# Aroca_EPS-v_2_0.net
KiCad netlist of a schematic drawn in EAGLE
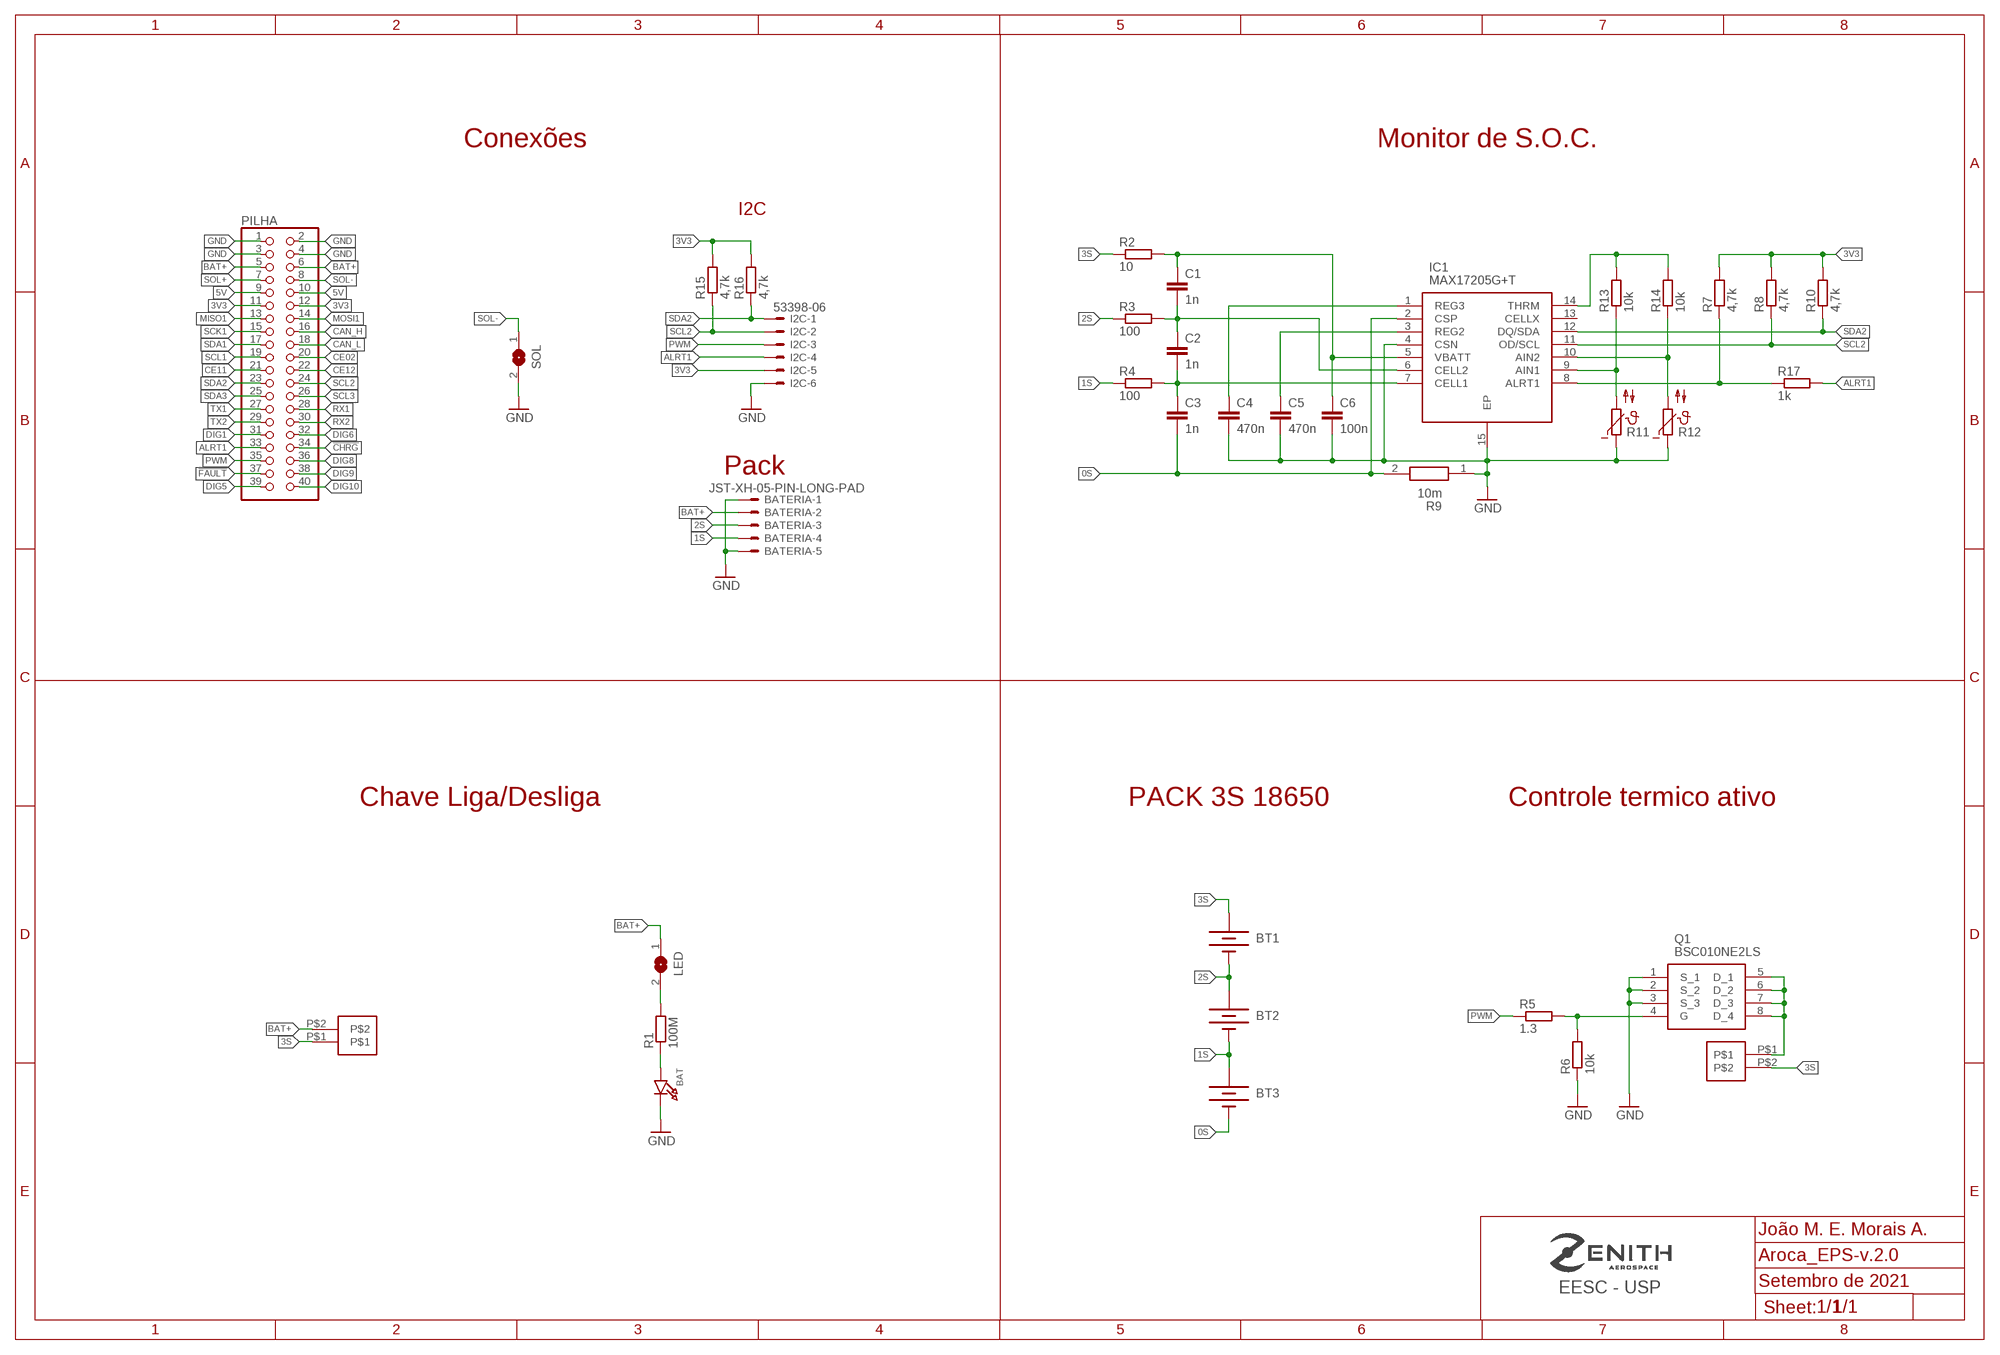
[diagram p0: schematic, sheet 1]

(export (version "E")
  (design (tool "Eeschema 10.0.6"))
  (components
    (comp (ref "BAT")
      (value "LED1206")
      (footprint "eagle-import:CHIPLED_1206")
      (libsource (lib "eagle-import") (part "LED1206"))
    )
    (comp (ref "BATERIA")
      (value "JST-XH-05-PIN-LONG-PAD")
      (footprint "eagle-import:JST-XH-05-PACKAGE-LONG-PAD")
      (libsource (lib "eagle-import") (part "JST-XH-05-PIN-LONG-PAD"))
    )
    (comp (ref "BT1")
      (value "BATTERY-18650")
      (footprint "eagle-import:BATTERY_18650-HOLDER")
      (libsource (lib "eagle-import") (part "BATTERY-18650"))
    )
    (comp (ref "BT2")
      (value "BATTERY-18650")
      (footprint "eagle-import:BATTERY_18650-HOLDER")
      (libsource (lib "eagle-import") (part "BATTERY-18650"))
    )
    (comp (ref "BT3")
      (value "BATTERY-18650")
      (footprint "eagle-import:BATTERY_18650-HOLDER")
      (libsource (lib "eagle-import") (part "BATTERY-18650"))
    )
    (comp (ref "C1")
      (value "1n")
      (footprint "eagle-import:C0805")
      (libsource (lib "eagle-import") (part "C-EUC0805"))
    )
    (comp (ref "C2")
      (value "1n")
      (footprint "eagle-import:C0805")
      (libsource (lib "eagle-import") (part "C-EUC0805"))
    )
    (comp (ref "C3")
      (value "1n")
      (footprint "eagle-import:C0805")
      (libsource (lib "eagle-import") (part "C-EUC0805"))
    )
    (comp (ref "C4")
      (value "470n")
      (footprint "eagle-import:C0805")
      (libsource (lib "eagle-import") (part "C-EUC0805"))
    )
    (comp (ref "C5")
      (value "470n")
      (footprint "eagle-import:C0805")
      (libsource (lib "eagle-import") (part "C-EUC0805"))
    )
    (comp (ref "C6")
      (value "100n")
      (footprint "eagle-import:C0805")
      (libsource (lib "eagle-import") (part "C-EUC0805"))
    )
    (comp (ref "I2C")
      (value "53398-06")
      (footprint "eagle-import:53398-06")
      (fields (field (name "MF") "MOLEX"))
      (libsource (lib "eagle-import") (part "53?-06398"))
    )
    (comp (ref "IC1")
      (value "MAX17205G+T")
      (footprint "eagle-import:SON40P300X300X80-15N")
      (fields (field (name "MOUSER_PART_NUMBER") "700-MAX17205G+T"))
      (libsource (lib "eagle-import") (part "MAX17205G+T"))
    )
    (comp (ref "LED")
      (value "SOLDERJUMPERREFLOW_NOPASTE")
      (footprint "eagle-import:SOLDERJUMPER_REFLOW_NOPASTE")
      (libsource (lib "eagle-import") (part "SOLDERJUMPERREFLOW_NOPASTE"))
    )
    (comp (ref "PILHA")
      (value "PINHD-2X20")
      (footprint "eagle-import:2X20")
      (libsource (lib "eagle-import") (part "PINHD-2X20"))
    )
    (comp (ref "Q1")
      (value "BSC010NE2LS")
      (footprint "eagle-import:PG-TDSON-8")
      (fields (field (name "MOUSER_PART_NUMBER") "726-BSC010NE2LS"))
      (libsource (lib "eagle-import") (part "BSC010NE2LS"))
    )
    (comp (ref "R1")
      (value "100M")
      (footprint "eagle-import:R0805")
      (libsource (lib "eagle-import") (part "R-EU_R0805"))
    )
    (comp (ref "R2")
      (value "10")
      (footprint "eagle-import:0204_7")
      (libsource (lib "eagle-import") (part "R-EU_0204/7"))
    )
    (comp (ref "R3")
      (value "100")
      (footprint "eagle-import:0204_7")
      (libsource (lib "eagle-import") (part "R-EU_0204/7"))
    )
    (comp (ref "R4")
      (value "100")
      (footprint "eagle-import:0204_7")
      (libsource (lib "eagle-import") (part "R-EU_0204/7"))
    )
    (comp (ref "R5")
      (value "1.3")
      (footprint "eagle-import:R0805")
      (libsource (lib "eagle-import") (part "R-EU_R0805"))
    )
    (comp (ref "R6")
      (value "10k")
      (footprint "eagle-import:R0805")
      (libsource (lib "eagle-import") (part "R-EU_R0805"))
    )
    (comp (ref "R7")
      (value "4,7k")
      (footprint "eagle-import:R0805")
      (libsource (lib "eagle-import") (part "R-EU_R0805"))
    )
    (comp (ref "R8")
      (value "4,7k")
      (footprint "eagle-import:R0805")
      (libsource (lib "eagle-import") (part "R-EU_R0805"))
    )
    (comp (ref "R9")
      (value "10m")
      (footprint "eagle-import:GMR320HJBFA10L0")
      (fields
        (field (name "MANUFACTURER_PART_NUMBER") "GMR320HJBFA10L0")
        (field (name "MOUSER_PART_NUMBER") "755-GMR320HJBFA10L0")
      )
      (libsource (lib "eagle-import") (part "GMR320HJBFA10L0"))
    )
    (comp (ref "R10")
      (value "4,7k")
      (footprint "eagle-import:R0805")
      (libsource (lib "eagle-import") (part "R-EU_R0805"))
    )
    (comp (ref "R11")
      (value "NTC640")
      (footprint "eagle-import:P640")
      (libsource (lib "eagle-import") (part "NTC640"))
    )
    (comp (ref "R12")
      (value "NTC640")
      (footprint "eagle-import:P640")
      (libsource (lib "eagle-import") (part "NTC640"))
    )
    (comp (ref "R13")
      (value "10k")
      (footprint "eagle-import:R0805")
      (libsource (lib "eagle-import") (part "R-EU_R0805"))
    )
    (comp (ref "R14")
      (value "10k")
      (footprint "eagle-import:R0805")
      (libsource (lib "eagle-import") (part "R-EU_R0805"))
    )
    (comp (ref "R15")
      (value "4,7k")
      (footprint "eagle-import:R0805")
      (libsource (lib "eagle-import") (part "R-EU_R0805"))
    )
    (comp (ref "R16")
      (value "4,7k")
      (footprint "eagle-import:R0805")
      (libsource (lib "eagle-import") (part "R-EU_R0805"))
    )
    (comp (ref "R17")
      (value "1k")
      (footprint "eagle-import:R0805")
      (libsource (lib "eagle-import") (part "R-EU_R0805"))
    )
    (comp (ref "SOL")
      (value "SOLDERJUMPERREFLOW_NOPASTE")
      (footprint "eagle-import:SOLDERJUMPER_REFLOW_NOPASTE")
      (libsource (lib "eagle-import") (part "SOLDERJUMPERREFLOW_NOPASTE"))
    )
    (comp (ref "U$1")
      (value "S02B-XASS-1")
      (footprint "eagle-import:S02B-XASS-1")
      (libsource (lib "eagle-import") (part "S02B-XASS-1"))
    )
    (comp (ref "U$2")
      (value "B02B-XASK-1")
      (footprint "eagle-import:B02B-XASK-1")
      (libsource (lib "eagle-import") (part "B02B-XASK-1"))
    )
  )
  (nets
    (net (code "1") (name "/~{CHRG}") (class "Default")
      (node (ref "PILHA") (pin "34") (pinfunction "34_34") (pintype "passive"))
    )
    (net (code "2") (name "/~{FAULT}") (class "Default")
      (node (ref "PILHA") (pin "37") (pinfunction "37_37") (pintype "passive"))
    )
    (net (code "3") (name "0S") (class "Default")
      (node (ref "BT3") (pin "GND@1") (pinfunction "-_GND@1") (pintype "power_in"))
      (node (ref "C3") (pin "2") (pinfunction "2_2") (pintype "passive"))
      (node (ref "IC1") (pin "2") (pinfunction "CSP_2") (pintype "bidirectional"))
      (node (ref "R9") (pin "2") (pinfunction "2_2") (pintype "bidirectional"))
    )
    (net (code "4") (name "1S") (class "Default")
      (node (ref "BATERIA") (pin "4") (pinfunction "S_4") (pintype "passive"))
      (node (ref "BT2") (pin "GND@1") (pinfunction "-_GND@1") (pintype "power_in"))
      (node (ref "BT3") (pin "PWR@1") (pinfunction "+_PWR@1") (pintype "power_in"))
      (node (ref "R4") (pin "1") (pinfunction "1_1") (pintype "passive"))
    )
    (net (code "5") (name "2S") (class "Default")
      (node (ref "BATERIA") (pin "3") (pinfunction "S_3") (pintype "passive"))
      (node (ref "BT1") (pin "GND@1") (pinfunction "-_GND@1") (pintype "power_in"))
      (node (ref "BT2") (pin "PWR@1") (pinfunction "+_PWR@1") (pintype "power_in"))
      (node (ref "R3") (pin "1") (pinfunction "1_1") (pintype "passive"))
    )
    (net (code "6") (name "3S") (class "Default")
      (node (ref "BT1") (pin "PWR@1") (pinfunction "+_PWR@1") (pintype "power_in"))
      (node (ref "R2") (pin "1") (pinfunction "1_1") (pintype "passive"))
      (node (ref "U$1") (pin "P$1") (pinfunction "P$1_P$1") (pintype "bidirectional"))
      (node (ref "U$2") (pin "P$2") (pinfunction "P$2_P$2") (pintype "bidirectional"))
    )
    (net (code "7") (name "3V3") (class "Default")
      (node (ref "I2C") (pin "5") (pinfunction "S_5") (pintype "passive"))
      (node (ref "PILHA") (pin "11") (pinfunction "11_11") (pintype "passive"))
      (node (ref "PILHA") (pin "12") (pinfunction "12_12") (pintype "passive"))
      (node (ref "R10") (pin "2") (pinfunction "2_2") (pintype "passive"))
      (node (ref "R15") (pin "2") (pinfunction "2_2") (pintype "passive"))
      (node (ref "R16") (pin "2") (pinfunction "2_2") (pintype "passive"))
      (node (ref "R7") (pin "2") (pinfunction "2_2") (pintype "passive"))
      (node (ref "R8") (pin "2") (pinfunction "2_2") (pintype "passive"))
    )
    (net (code "8") (name "5V") (class "Default")
      (node (ref "PILHA") (pin "10") (pinfunction "10_10") (pintype "passive"))
      (node (ref "PILHA") (pin "9") (pinfunction "9_9") (pintype "passive"))
    )
    (net (code "9") (name "ALRT1") (class "Default")
      (node (ref "I2C") (pin "4") (pinfunction "S_4") (pintype "passive"))
      (node (ref "PILHA") (pin "33") (pinfunction "33_33") (pintype "passive"))
      (node (ref "R17") (pin "2") (pinfunction "2_2") (pintype "passive"))
    )
    (net (code "10") (name "BAT+") (class "Default")
      (node (ref "BATERIA") (pin "2") (pinfunction "S_2") (pintype "passive"))
      (node (ref "LED") (pin "1") (pinfunction "1_1") (pintype "passive"))
      (node (ref "PILHA") (pin "5") (pinfunction "5_5") (pintype "passive"))
      (node (ref "PILHA") (pin "6") (pinfunction "6_6") (pintype "passive"))
      (node (ref "U$1") (pin "P$2") (pinfunction "P$2_P$2") (pintype "bidirectional"))
    )
    (net (code "11") (name "CAN_H") (class "Default")
      (node (ref "PILHA") (pin "16") (pinfunction "16_16") (pintype "passive"))
    )
    (net (code "12") (name "CAN_L") (class "Default")
      (node (ref "PILHA") (pin "18") (pinfunction "18_18") (pintype "passive"))
    )
    (net (code "13") (name "CE02") (class "Default")
      (node (ref "PILHA") (pin "20") (pinfunction "20_20") (pintype "passive"))
    )
    (net (code "14") (name "CE11") (class "Default")
      (node (ref "PILHA") (pin "21") (pinfunction "21_21") (pintype "passive"))
    )
    (net (code "15") (name "CE12") (class "Default")
      (node (ref "PILHA") (pin "22") (pinfunction "22_22") (pintype "passive"))
    )
    (net (code "16") (name "DIG1") (class "Default")
      (node (ref "PILHA") (pin "31") (pinfunction "31_31") (pintype "passive"))
    )
    (net (code "17") (name "DIG5") (class "Default")
      (node (ref "PILHA") (pin "39") (pinfunction "39_39") (pintype "passive"))
    )
    (net (code "18") (name "DIG6") (class "Default")
      (node (ref "PILHA") (pin "32") (pinfunction "32_32") (pintype "passive"))
    )
    (net (code "19") (name "DIG8") (class "Default")
      (node (ref "PILHA") (pin "36") (pinfunction "36_36") (pintype "passive"))
    )
    (net (code "20") (name "DIG9") (class "Default")
      (node (ref "PILHA") (pin "38") (pinfunction "38_38") (pintype "passive"))
    )
    (net (code "21") (name "DIG10") (class "Default")
      (node (ref "PILHA") (pin "40") (pinfunction "40_40") (pintype "passive"))
    )
    (net (code "22") (name "GND") (class "Default")
      (node (ref "BAT") (pin "C") (pinfunction "C_C") (pintype "passive"))
      (node (ref "BATERIA") (pin "1") (pinfunction "S_1") (pintype "passive"))
      (node (ref "BATERIA") (pin "5") (pinfunction "S_5") (pintype "passive"))
      (node (ref "C4") (pin "2") (pinfunction "2_2") (pintype "passive"))
      (node (ref "C5") (pin "2") (pinfunction "2_2") (pintype "passive"))
      (node (ref "C6") (pin "2") (pinfunction "2_2") (pintype "passive"))
      (node (ref "I2C") (pin "6") (pinfunction "S_6") (pintype "passive"))
      (node (ref "IC1") (pin "15") (pinfunction "EP_15") (pintype "bidirectional"))
      (node (ref "IC1") (pin "4") (pinfunction "CSN_4") (pintype "bidirectional"))
      (node (ref "PILHA") (pin "1") (pinfunction "1_1") (pintype "passive"))
      (node (ref "PILHA") (pin "2") (pinfunction "2_2") (pintype "passive"))
      (node (ref "PILHA") (pin "3") (pinfunction "3_3") (pintype "passive"))
      (node (ref "PILHA") (pin "4") (pinfunction "4_4") (pintype "passive"))
      (node (ref "Q1") (pin "1") (pinfunction "S_1_1") (pintype "bidirectional"))
      (node (ref "Q1") (pin "2") (pinfunction "S_2_2") (pintype "bidirectional"))
      (node (ref "Q1") (pin "3") (pinfunction "S_3_3") (pintype "bidirectional"))
      (node (ref "R11") (pin "1") (pinfunction "1_1") (pintype "passive"))
      (node (ref "R12") (pin "1") (pinfunction "1_1") (pintype "passive"))
      (node (ref "R6") (pin "1") (pinfunction "1_1") (pintype "passive"))
      (node (ref "R9") (pin "1") (pinfunction "1_1") (pintype "bidirectional"))
      (node (ref "SOL") (pin "2") (pinfunction "2_2") (pintype "passive"))
    )
    (net (code "23") (name "MISO1") (class "Default")
      (node (ref "PILHA") (pin "13") (pinfunction "13_13") (pintype "passive"))
    )
    (net (code "24") (name "MOSI1") (class "Default")
      (node (ref "PILHA") (pin "14") (pinfunction "14_14") (pintype "passive"))
    )
    (net (code "25") (name "Net-(BAT-PadA)") (class "Default")
      (node (ref "BAT") (pin "A") (pinfunction "A_A") (pintype "passive"))
      (node (ref "R1") (pin "1") (pinfunction "1_1") (pintype "passive"))
    )
    (net (code "26") (name "Net-(IC1-AIN1)") (class "Default")
      (node (ref "IC1") (pin "9") (pinfunction "AIN1_9") (pintype "bidirectional"))
      (node (ref "R11") (pin "2") (pinfunction "2_2") (pintype "passive"))
      (node (ref "R13") (pin "1") (pinfunction "1_1") (pintype "passive"))
    )
    (net (code "27") (name "Net-(IC1-AIN2)") (class "Default")
      (node (ref "IC1") (pin "10") (pinfunction "AIN2_10") (pintype "bidirectional"))
      (node (ref "R12") (pin "2") (pinfunction "2_2") (pintype "passive"))
      (node (ref "R14") (pin "1") (pinfunction "1_1") (pintype "passive"))
    )
    (net (code "28") (name "Net-(IC1-ALRT1)") (class "Default")
      (node (ref "IC1") (pin "8") (pinfunction "ALRT1_8") (pintype "bidirectional"))
      (node (ref "R17") (pin "1") (pinfunction "1_1") (pintype "passive"))
      (node (ref "R7") (pin "1") (pinfunction "1_1") (pintype "passive"))
    )
    (net (code "29") (name "Net-(IC1-CELL1)") (class "Default")
      (node (ref "C2") (pin "2") (pinfunction "2_2") (pintype "passive"))
      (node (ref "C3") (pin "1") (pinfunction "1_1") (pintype "passive"))
      (node (ref "IC1") (pin "7") (pinfunction "CELL1_7") (pintype "bidirectional"))
      (node (ref "R4") (pin "2") (pinfunction "2_2") (pintype "passive"))
    )
    (net (code "30") (name "Net-(IC1-CELL2)") (class "Default")
      (node (ref "C1") (pin "2") (pinfunction "2_2") (pintype "passive"))
      (node (ref "C2") (pin "1") (pinfunction "1_1") (pintype "passive"))
      (node (ref "IC1") (pin "6") (pinfunction "CELL2_6") (pintype "bidirectional"))
      (node (ref "R3") (pin "2") (pinfunction "2_2") (pintype "passive"))
    )
    (net (code "31") (name "Net-(IC1-REG2)") (class "Default")
      (node (ref "C5") (pin "1") (pinfunction "1_1") (pintype "passive"))
      (node (ref "IC1") (pin "3") (pinfunction "REG2_3") (pintype "bidirectional"))
    )
    (net (code "32") (name "Net-(IC1-REG3)") (class "Default")
      (node (ref "C4") (pin "1") (pinfunction "1_1") (pintype "passive"))
      (node (ref "IC1") (pin "1") (pinfunction "REG3_1") (pintype "bidirectional"))
    )
    (net (code "33") (name "Net-(IC1-THRM)") (class "Default")
      (node (ref "IC1") (pin "14") (pinfunction "THRM_14") (pintype "bidirectional"))
      (node (ref "R13") (pin "2") (pinfunction "2_2") (pintype "passive"))
      (node (ref "R14") (pin "2") (pinfunction "2_2") (pintype "passive"))
    )
    (net (code "34") (name "Net-(IC1-VBATT)") (class "Default")
      (node (ref "C1") (pin "1") (pinfunction "1_1") (pintype "passive"))
      (node (ref "C6") (pin "1") (pinfunction "1_1") (pintype "passive"))
      (node (ref "IC1") (pin "5") (pinfunction "VBATT_5") (pintype "bidirectional"))
      (node (ref "R2") (pin "2") (pinfunction "2_2") (pintype "passive"))
    )
    (net (code "35") (name "Net-(LED-Pad2)") (class "Default")
      (node (ref "LED") (pin "2") (pinfunction "2_2") (pintype "passive"))
      (node (ref "R1") (pin "2") (pinfunction "2_2") (pintype "passive"))
    )
    (net (code "36") (name "Net-(Q1-D_1)") (class "Default")
      (node (ref "Q1") (pin "5") (pinfunction "D_1_5") (pintype "bidirectional"))
      (node (ref "Q1") (pin "6") (pinfunction "D_2_6") (pintype "bidirectional"))
      (node (ref "Q1") (pin "7") (pinfunction "D_3_7") (pintype "bidirectional"))
      (node (ref "Q1") (pin "8") (pinfunction "D_4_8") (pintype "bidirectional"))
      (node (ref "U$2") (pin "P$1") (pinfunction "P$1_P$1") (pintype "bidirectional"))
    )
    (net (code "37") (name "Net-(Q1-G)") (class "Default")
      (node (ref "Q1") (pin "4") (pinfunction "G_4") (pintype "bidirectional"))
      (node (ref "R5") (pin "2") (pinfunction "2_2") (pintype "passive"))
      (node (ref "R6") (pin "2") (pinfunction "2_2") (pintype "passive"))
    )
    (net (code "38") (name "PWM") (class "Default")
      (node (ref "I2C") (pin "3") (pinfunction "S_3") (pintype "passive"))
      (node (ref "PILHA") (pin "35") (pinfunction "35_35") (pintype "passive"))
      (node (ref "R5") (pin "1") (pinfunction "1_1") (pintype "passive"))
    )
    (net (code "39") (name "RX1") (class "Default")
      (node (ref "PILHA") (pin "28") (pinfunction "28_28") (pintype "passive"))
    )
    (net (code "40") (name "RX2") (class "Default")
      (node (ref "PILHA") (pin "30") (pinfunction "30_30") (pintype "passive"))
    )
    (net (code "41") (name "SCK1") (class "Default")
      (node (ref "PILHA") (pin "15") (pinfunction "15_15") (pintype "passive"))
    )
    (net (code "42") (name "SCL1") (class "Default")
      (node (ref "PILHA") (pin "19") (pinfunction "19_19") (pintype "passive"))
    )
    (net (code "43") (name "SCL2") (class "Default")
      (node (ref "I2C") (pin "2") (pinfunction "S_2") (pintype "passive"))
      (node (ref "IC1") (pin "11") (pinfunction "OD/SCL_11") (pintype "bidirectional"))
      (node (ref "PILHA") (pin "24") (pinfunction "24_24") (pintype "passive"))
      (node (ref "R15") (pin "1") (pinfunction "1_1") (pintype "passive"))
      (node (ref "R8") (pin "1") (pinfunction "1_1") (pintype "passive"))
    )
    (net (code "44") (name "SCL3") (class "Default")
      (node (ref "PILHA") (pin "26") (pinfunction "26_26") (pintype "passive"))
    )
    (net (code "45") (name "SDA1") (class "Default")
      (node (ref "PILHA") (pin "17") (pinfunction "17_17") (pintype "passive"))
    )
    (net (code "46") (name "SDA2") (class "Default")
      (node (ref "I2C") (pin "1") (pinfunction "S_1") (pintype "passive"))
      (node (ref "IC1") (pin "12") (pinfunction "DQ/SDA_12") (pintype "bidirectional"))
      (node (ref "PILHA") (pin "23") (pinfunction "23_23") (pintype "passive"))
      (node (ref "R10") (pin "1") (pinfunction "1_1") (pintype "passive"))
      (node (ref "R16") (pin "1") (pinfunction "1_1") (pintype "passive"))
    )
    (net (code "47") (name "SDA3") (class "Default")
      (node (ref "PILHA") (pin "25") (pinfunction "25_25") (pintype "passive"))
    )
    (net (code "48") (name "SOL+") (class "Default")
      (node (ref "PILHA") (pin "7") (pinfunction "7_7") (pintype "passive"))
    )
    (net (code "49") (name "SOL-") (class "Default")
      (node (ref "PILHA") (pin "8") (pinfunction "8_8") (pintype "passive"))
      (node (ref "SOL") (pin "1") (pinfunction "1_1") (pintype "passive"))
    )
    (net (code "50") (name "TX1") (class "Default")
      (node (ref "PILHA") (pin "27") (pinfunction "27_27") (pintype "passive"))
    )
    (net (code "51") (name "TX2") (class "Default")
      (node (ref "PILHA") (pin "29") (pinfunction "29_29") (pintype "passive"))
    )
    (net (code "52") (name "unconnected-(IC1-CELLX-Pad13)") (class "Default")
      (node (ref "IC1") (pin "13") (pinfunction "CELLX_13") (pintype "bidirectional"))
    )
  )
)
